# 9-ZIGBEE.net
KiCad netlist of a schematic drawn in Altium Designer
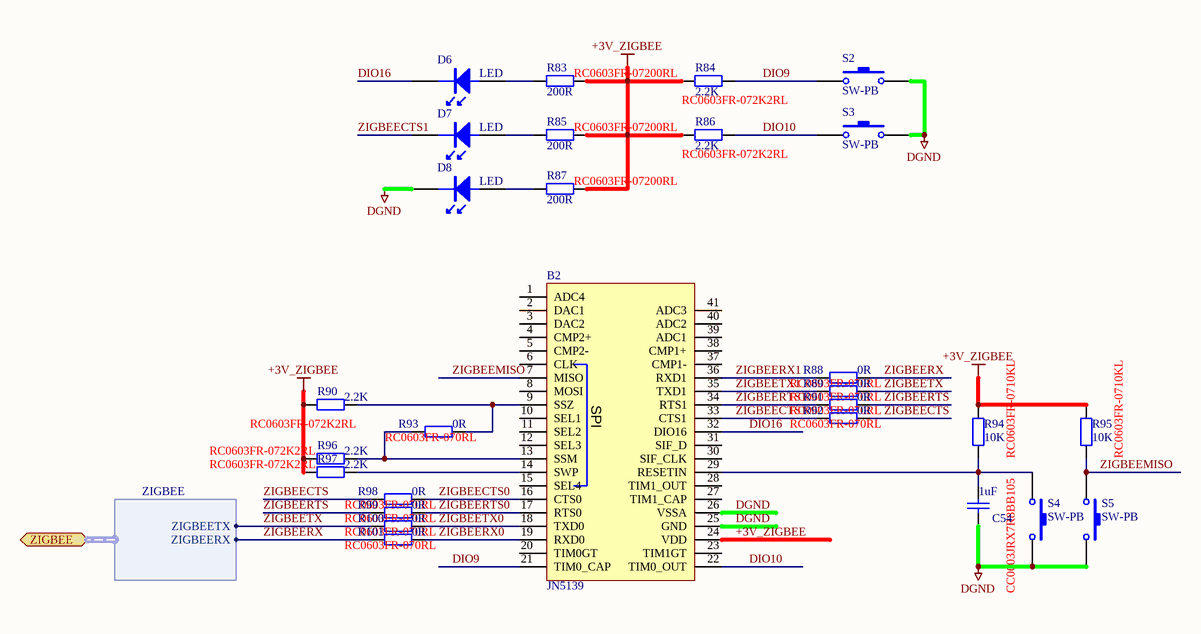
[diagram p0: 9-ZIGBEE.SchDoc]

(export (version "E")
  (design (tool "Eeschema 10.0.6"))
  (components
    (comp (ref "B2") (value "JN5139") (footprint "JN5139") (libsource (lib "Blocks") (part "JN5139")))
    (comp (ref "C54")
      (value "1uF")
      (footprint "CC0603")
      (description "Capacitor")
      (fields (field (name "TYPE NO.") "CC0603JRX7R8BB105"))
      (libsource (lib "Miscellaneous Devices") (part "Cap"))
    )
    (comp (ref "D6") (value "LED") (footprint "D0603") (libsource (lib "Discrete") (part "LED")))
    (comp (ref "D7") (value "LED") (footprint "Discrete-SMT:D0603") (libsource (lib "Discrete") (part "LED")))
    (comp (ref "D8") (value "LED") (footprint "D0603") (libsource (lib "Discrete") (part "LED")))
    (comp (ref "R83")
      (value "200R")
      (footprint "CC0603")
      (description "Resistor")
      (fields (field (name "TYPE NO.") "RC0603FR-07200RL"))
      (libsource (lib "Miscellaneous Devices") (part "Res2"))
    )
    (comp (ref "R84")
      (value "2.2K")
      (footprint "CC0603")
      (description "Resistor")
      (fields (field (name "TYPE NO.") "RC0603FR-072K2RL"))
      (libsource (lib "Miscellaneous Devices") (part "Res2"))
    )
    (comp (ref "R85")
      (value "200R")
      (footprint "CC0603")
      (description "Resistor")
      (fields (field (name "TYPE NO.") "RC0603FR-07200RL"))
      (libsource (lib "Miscellaneous Devices") (part "Res2"))
    )
    (comp (ref "R86")
      (value "2.2K")
      (footprint "CC0603")
      (description "Resistor")
      (fields (field (name "TYPE NO.") "RC0603FR-072K2RL"))
      (libsource (lib "Miscellaneous Devices") (part "Res2"))
    )
    (comp (ref "R87")
      (value "200R")
      (footprint "CC0603")
      (description "Resistor")
      (fields (field (name "TYPE NO.") "RC0603FR-07200RL"))
      (libsource (lib "Miscellaneous Devices") (part "Res2"))
    )
    (comp (ref "R88")
      (value "0R")
      (footprint "CC0603")
      (description "Resistor")
      (fields (field (name "TYPE NO.") "RC0603FR-070RL"))
      (libsource (lib "") (part "Res2_1"))
    )
    (comp (ref "R89")
      (value "0R")
      (footprint "CC0603")
      (description "Resistor")
      (fields (field (name "TYPE NO.") "RC0603FR-070RL"))
      (libsource (lib "") (part "Res2_1"))
    )
    (comp (ref "R90")
      (value "2.2K")
      (footprint "CC0603")
      (description "Resistor")
      (fields (field (name "TYPE NO.") "RC0603FR-072K2RL"))
      (libsource (lib "Miscellaneous Devices") (part "Res2"))
    )
    (comp (ref "R91")
      (value "0R")
      (footprint "CC0603")
      (description "Resistor")
      (fields (field (name "TYPE NO.") "RC0603FR-070RL"))
      (libsource (lib "") (part "Res2_1"))
    )
    (comp (ref "R92")
      (value "0R")
      (footprint "CC0603")
      (description "Resistor")
      (fields (field (name "TYPE NO.") "RC0603FR-070RL"))
      (libsource (lib "") (part "Res2_1"))
    )
    (comp (ref "R93")
      (value "0R")
      (footprint "CC0603")
      (description "Resistor")
      (fields (field (name "TYPE NO.") "RC0603FR-070RL"))
      (libsource (lib "") (part "Res2_1"))
    )
    (comp (ref "R94")
      (value "10K")
      (footprint "CC0603")
      (description "Resistor")
      (fields (field (name "TYPE NO.") "RC0603FR-0710KL"))
      (libsource (lib "") (part "Res2_2"))
    )
    (comp (ref "R95")
      (value "10K")
      (footprint "CC0603")
      (description "Resistor")
      (fields (field (name "TYPE NO.") "RC0603FR-0710KL"))
      (libsource (lib "") (part "Res2_2"))
    )
    (comp (ref "R96")
      (value "2.2K")
      (footprint "CC0603")
      (description "Resistor")
      (fields (field (name "TYPE NO.") "RC0603FR-072K2RL"))
      (libsource (lib "Miscellaneous Devices") (part "Res2"))
    )
    (comp (ref "R97")
      (value "2.2K")
      (footprint "CC0603")
      (description "Resistor")
      (fields (field (name "TYPE NO.") "RC0603FR-072K2RL"))
      (libsource (lib "Miscellaneous Devices") (part "Res2"))
    )
    (comp (ref "R98")
      (value "0R")
      (footprint "CC0603")
      (description "Resistor")
      (fields (field (name "TYPE NO.") "RC0603FR-070RL"))
      (libsource (lib "") (part "Res2_1"))
    )
    (comp (ref "R99")
      (value "0R")
      (footprint "CC0603")
      (description "Resistor")
      (fields (field (name "TYPE NO.") "RC0603FR-070RL"))
      (libsource (lib "") (part "Res2_1"))
    )
    (comp (ref "R100")
      (value "0R")
      (footprint "CC0603")
      (description "Resistor")
      (fields (field (name "TYPE NO.") "RC0603FR-070RL"))
      (libsource (lib "") (part "Res2_1"))
    )
    (comp (ref "R101")
      (value "0R")
      (footprint "CC0603")
      (description "Resistor")
      (fields (field (name "TYPE NO.") "RC0603FR-070RL"))
      (libsource (lib "") (part "Res2_1"))
    )
    (comp (ref "S2")
      (value "SW-PB")
      (footprint "SPST")
      (description "Switch")
      (fields (field (name "PUBLISHER") "Altium Limited"))
      (libsource (lib "Miscellaneous Devices") (part "SW-PB"))
    )
    (comp (ref "S3")
      (value "SW-PB")
      (footprint "SPST")
      (description "Switch")
      (fields (field (name "PUBLISHER") "Altium Limited"))
      (libsource (lib "Miscellaneous Devices") (part "SW-PB"))
    )
    (comp (ref "S4")
      (value "SW-PB")
      (footprint "SPST")
      (description "Switch")
      (fields (field (name "PUBLISHER") "Altium Limited"))
      (libsource (lib "Miscellaneous Devices") (part "SW-PB"))
    )
    (comp (ref "S5")
      (value "SW-PB")
      (footprint "SPST")
      (description "Switch")
      (fields (field (name "PUBLISHER") "Altium Limited"))
      (libsource (lib "Miscellaneous Devices") (part "SW-PB"))
    )
  )
  (nets
    (net (code "2") (name "+3V_ZIGBEE") (class "Default")
      (node (ref "B2") (pin "24") (pinfunction "VDD_24") (pintype "passive"))
      (node (ref "R83") (pin "2") (pinfunction "2_2") (pintype "passive"))
      (node (ref "R84") (pin "1") (pinfunction "1_1") (pintype "passive"))
      (node (ref "R85") (pin "2") (pinfunction "2_2") (pintype "passive"))
      (node (ref "R86") (pin "1") (pinfunction "1_1") (pintype "passive"))
      (node (ref "R87") (pin "2") (pinfunction "2_2") (pintype "passive"))
      (node (ref "R90") (pin "1") (pinfunction "1_1") (pintype "passive"))
      (node (ref "R94") (pin "1") (pinfunction "1_1") (pintype "passive"))
      (node (ref "R95") (pin "1") (pinfunction "1_1") (pintype "passive"))
      (node (ref "R96") (pin "1") (pinfunction "1_1") (pintype "passive"))
      (node (ref "R97") (pin "1") (pinfunction "1_1") (pintype "passive"))
    )
    (net (code "3") (name "/DIO9") (class "Default")
      (node (ref "B2") (pin "21") (pinfunction "TIM0_CAP_21") (pintype "passive"))
      (node (ref "R84") (pin "2") (pinfunction "2_2") (pintype "passive"))
      (node (ref "S2") (pin "1") (pinfunction "1_1") (pintype "passive"))
    )
    (net (code "4") (name "/DIO10") (class "Default")
      (node (ref "B2") (pin "22") (pinfunction "TIM0_OUT_22") (pintype "passive"))
      (node (ref "R86") (pin "2") (pinfunction "2_2") (pintype "passive"))
      (node (ref "S3") (pin "1") (pinfunction "1_1") (pintype "passive"))
    )
    (net (code "5") (name "/DIO16") (class "Default")
      (node (ref "B2") (pin "32") (pinfunction "DIO16_32") (pintype "passive"))
      (node (ref "D6") (pin "2") (pinfunction "K_2") (pintype "passive"))
    )
    (net (code "6") (name "/ZIGBEECTS") (class "Default")
      (node (ref "R92") (pin "1") (pinfunction "1_1") (pintype "passive"))
      (node (ref "R98") (pin "2") (pinfunction "2_2") (pintype "passive"))
    )
    (net (code "7") (name "/ZIGBEECTS0") (class "Default")
      (node (ref "B2") (pin "16") (pinfunction "CTS0_16") (pintype "passive"))
      (node (ref "R98") (pin "1") (pinfunction "1_1") (pintype "passive"))
    )
    (net (code "8") (name "/ZIGBEECTS1") (class "Default")
      (node (ref "B2") (pin "33") (pinfunction "CTS1_33") (pintype "passive"))
      (node (ref "D7") (pin "2") (pinfunction "K_2") (pintype "passive"))
      (node (ref "R92") (pin "2") (pinfunction "2_2") (pintype "passive"))
    )
    (net (code "9") (name "/ZIGBEEMISO") (class "Default")
      (node (ref "B2") (pin "7") (pinfunction "MISO_7") (pintype "passive"))
      (node (ref "R95") (pin "2") (pinfunction "2_2") (pintype "passive"))
      (node (ref "S5") (pin "1") (pinfunction "1_1") (pintype "passive"))
    )
    (net (code "10") (name "/ZIGBEERTS") (class "Default")
      (node (ref "R91") (pin "1") (pinfunction "1_1") (pintype "passive"))
      (node (ref "R99") (pin "2") (pinfunction "2_2") (pintype "passive"))
    )
    (net (code "11") (name "/ZIGBEERTS0") (class "Default")
      (node (ref "B2") (pin "17") (pinfunction "RTS0_17") (pintype "passive"))
      (node (ref "R99") (pin "1") (pinfunction "1_1") (pintype "passive"))
    )
    (net (code "12") (name "/ZIGBEERTS1") (class "Default")
      (node (ref "B2") (pin "34") (pinfunction "RTS1_34") (pintype "passive"))
      (node (ref "R91") (pin "2") (pinfunction "2_2") (pintype "passive"))
    )
    (net (code "13") (name "/ZIGBEERX") (class "Default")
      (node (ref "R101") (pin "2") (pinfunction "2_2") (pintype "passive"))
      (node (ref "R88") (pin "1") (pinfunction "1_1") (pintype "passive"))
    )
    (net (code "14") (name "/ZIGBEERX0") (class "Default")
      (node (ref "B2") (pin "19") (pinfunction "RXD0_19") (pintype "passive"))
      (node (ref "R101") (pin "1") (pinfunction "1_1") (pintype "passive"))
    )
    (net (code "15") (name "/ZIGBEERX1") (class "Default")
      (node (ref "B2") (pin "36") (pinfunction "RXD1_36") (pintype "passive"))
      (node (ref "R88") (pin "2") (pinfunction "2_2") (pintype "passive"))
    )
    (net (code "16") (name "/ZIGBEETX") (class "Default")
      (node (ref "R100") (pin "2") (pinfunction "2_2") (pintype "passive"))
      (node (ref "R89") (pin "1") (pinfunction "1_1") (pintype "passive"))
    )
    (net (code "17") (name "/ZIGBEETX0") (class "Default")
      (node (ref "B2") (pin "18") (pinfunction "TXD0_18") (pintype "passive"))
      (node (ref "R100") (pin "1") (pinfunction "1_1") (pintype "passive"))
    )
    (net (code "18") (name "/ZIGBEETX1") (class "Default")
      (node (ref "B2") (pin "35") (pinfunction "TXD1_35") (pintype "passive"))
      (node (ref "R89") (pin "2") (pinfunction "2_2") (pintype "passive"))
    )
    (net (code "20") (name "DGND") (class "Default")
      (node (ref "B2") (pin "25") (pinfunction "GND_25") (pintype "passive"))
      (node (ref "B2") (pin "26") (pinfunction "VSSA_26") (pintype "passive"))
      (node (ref "C54") (pin "1") (pinfunction "1_1") (pintype "passive"))
      (node (ref "D8") (pin "2") (pinfunction "K_2") (pintype "passive"))
      (node (ref "S2") (pin "2") (pinfunction "2_2") (pintype "passive"))
      (node (ref "S3") (pin "2") (pinfunction "2_2") (pintype "passive"))
      (node (ref "S4") (pin "2") (pinfunction "2_2") (pintype "passive"))
      (node (ref "S5") (pin "2") (pinfunction "2_2") (pintype "passive"))
    )
    (net (code "21") (name "Net-(B2-RESETIN)") (class "Default")
      (node (ref "B2") (pin "29") (pinfunction "RESETIN_29") (pintype "passive"))
      (node (ref "C54") (pin "2") (pinfunction "2_2") (pintype "passive"))
      (node (ref "R94") (pin "2") (pinfunction "2_2") (pintype "passive"))
      (node (ref "S4") (pin "1") (pinfunction "1_1") (pintype "passive"))
    )
    (net (code "22") (name "Net-(B2-SSM)") (class "Default")
      (node (ref "B2") (pin "13") (pinfunction "SSM_13") (pintype "passive"))
      (node (ref "R93") (pin "2") (pinfunction "2_2") (pintype "passive"))
      (node (ref "R96") (pin "2") (pinfunction "2_2") (pintype "passive"))
    )
    (net (code "23") (name "Net-(B2-SSZ)") (class "Default")
      (node (ref "B2") (pin "9") (pinfunction "SSZ_9") (pintype "passive"))
      (node (ref "R90") (pin "2") (pinfunction "2_2") (pintype "passive"))
      (node (ref "R93") (pin "1") (pinfunction "1_1") (pintype "passive"))
    )
    (net (code "24") (name "Net-(B2-SWP)") (class "Default")
      (node (ref "B2") (pin "14") (pinfunction "SWP_14") (pintype "passive"))
      (node (ref "R97") (pin "2") (pinfunction "2_2") (pintype "passive"))
    )
    (net (code "25") (name "Net-(D6-A)") (class "Default")
      (node (ref "D6") (pin "1") (pinfunction "A_1") (pintype "passive"))
      (node (ref "R83") (pin "1") (pinfunction "1_1") (pintype "passive"))
    )
    (net (code "26") (name "Net-(D7-A)") (class "Default")
      (node (ref "D7") (pin "1") (pinfunction "A_1") (pintype "passive"))
      (node (ref "R85") (pin "1") (pinfunction "1_1") (pintype "passive"))
    )
    (net (code "27") (name "Net-(D8-A)") (class "Default")
      (node (ref "D8") (pin "1") (pinfunction "A_1") (pintype "passive"))
      (node (ref "R87") (pin "1") (pinfunction "1_1") (pintype "passive"))
    )
    (net (code "28") (name "unconnected-(B2-ADC1-Pad39)") (class "Default")
      (node (ref "B2") (pin "39") (pinfunction "ADC1_39") (pintype "passive"))
    )
    (net (code "29") (name "unconnected-(B2-ADC2-Pad40)") (class "Default")
      (node (ref "B2") (pin "40") (pinfunction "ADC2_40") (pintype "passive"))
    )
    (net (code "30") (name "unconnected-(B2-ADC3-Pad41)") (class "Default")
      (node (ref "B2") (pin "41") (pinfunction "ADC3_41") (pintype "passive"))
    )
    (net (code "31") (name "unconnected-(B2-ADC4-Pad1)") (class "Default")
      (node (ref "B2") (pin "1") (pinfunction "ADC4_1") (pintype "passive"))
    )
    (net (code "32") (name "unconnected-(B2-CLK-Pad6)") (class "Default")
      (node (ref "B2") (pin "6") (pinfunction "CLK_6") (pintype "passive"))
    )
    (net (code "33") (name "unconnected-(B2-CMP1+-Pad38)") (class "Default")
      (node (ref "B2") (pin "38") (pinfunction "CMP1+_38") (pintype "passive"))
    )
    (net (code "34") (name "unconnected-(B2-CMP1--Pad37)") (class "Default")
      (node (ref "B2") (pin "37") (pinfunction "CMP1-_37") (pintype "passive"))
    )
    (net (code "35") (name "unconnected-(B2-CMP2+-Pad4)") (class "Default")
      (node (ref "B2") (pin "4") (pinfunction "CMP2+_4") (pintype "passive"))
    )
    (net (code "36") (name "unconnected-(B2-CMP2--Pad5)") (class "Default")
      (node (ref "B2") (pin "5") (pinfunction "CMP2-_5") (pintype "passive"))
    )
    (net (code "37") (name "unconnected-(B2-DAC1-Pad2)") (class "Default")
      (node (ref "B2") (pin "2") (pinfunction "DAC1_2") (pintype "passive"))
    )
    (net (code "38") (name "unconnected-(B2-DAC2-Pad3)") (class "Default")
      (node (ref "B2") (pin "3") (pinfunction "DAC2_3") (pintype "passive"))
    )
    (net (code "39") (name "unconnected-(B2-MOSI-Pad8)") (class "Default")
      (node (ref "B2") (pin "8") (pinfunction "MOSI_8") (pintype "passive"))
    )
    (net (code "40") (name "unconnected-(B2-SEL1-Pad10)") (class "Default")
      (node (ref "B2") (pin "10") (pinfunction "SEL1_10") (pintype "passive"))
    )
    (net (code "41") (name "unconnected-(B2-SEL2-Pad11)") (class "Default")
      (node (ref "B2") (pin "11") (pinfunction "SEL2_11") (pintype "passive"))
    )
    (net (code "42") (name "unconnected-(B2-SEL3-Pad12)") (class "Default")
      (node (ref "B2") (pin "12") (pinfunction "SEL3_12") (pintype "passive"))
    )
    (net (code "43") (name "unconnected-(B2-SEL4-Pad15)") (class "Default")
      (node (ref "B2") (pin "15") (pinfunction "SEL4_15") (pintype "passive"))
    )
    (net (code "44") (name "unconnected-(B2-SIF_CLK-Pad30)") (class "Default")
      (node (ref "B2") (pin "30") (pinfunction "SIF_CLK_30") (pintype "passive"))
    )
    (net (code "45") (name "unconnected-(B2-SIF_D-Pad31)") (class "Default")
      (node (ref "B2") (pin "31") (pinfunction "SIF_D_31") (pintype "passive"))
    )
    (net (code "46") (name "unconnected-(B2-TIM0GT-Pad20)") (class "Default")
      (node (ref "B2") (pin "20") (pinfunction "TIM0GT_20") (pintype "passive"))
    )
    (net (code "47") (name "unconnected-(B2-TIM1GT-Pad23)") (class "Default")
      (node (ref "B2") (pin "23") (pinfunction "TIM1GT_23") (pintype "passive"))
    )
    (net (code "48") (name "unconnected-(B2-TIM1_CAP-Pad27)") (class "Default")
      (node (ref "B2") (pin "27") (pinfunction "TIM1_CAP_27") (pintype "passive"))
    )
    (net (code "49") (name "unconnected-(B2-TIM1_OUT-Pad28)") (class "Default")
      (node (ref "B2") (pin "28") (pinfunction "TIM1_OUT_28") (pintype "passive"))
    )
  )
)
